# WS2812B-strip.net
KiCad netlist of a schematic drawn in EAGLE
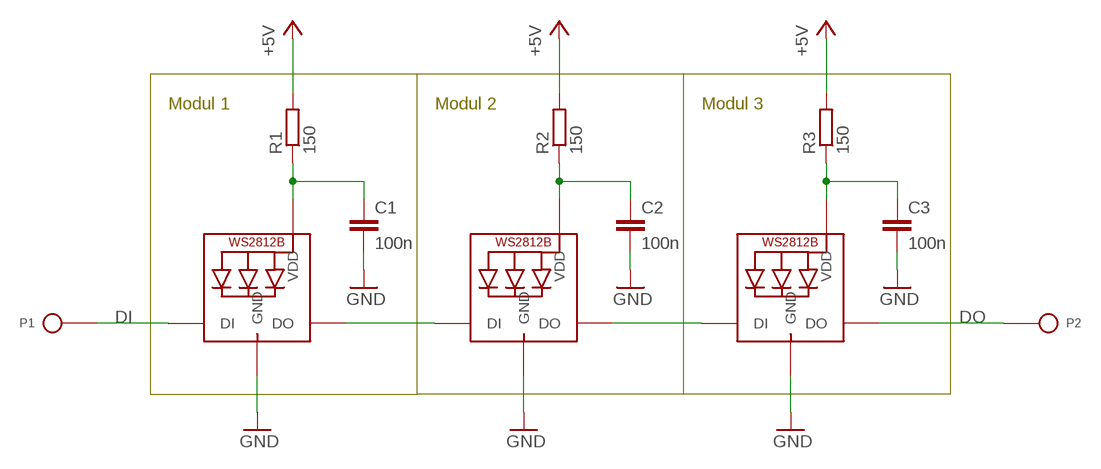
[diagram p0: schematic, sheet 1]

(export (version "E")
  (design (tool "Eeschema 10.0.6"))
  (components
    (comp (ref "C1")
      (value "100n")
      (footprint "eagle-import:C0805")
      (libsource (lib "eagle-import") (part "C-EUC0805"))
    )
    (comp (ref "C2")
      (value "100n")
      (footprint "eagle-import:C0805")
      (libsource (lib "eagle-import") (part "C-EUC0805"))
    )
    (comp (ref "C3")
      (value "100n")
      (footprint "eagle-import:C0805")
      (libsource (lib "eagle-import") (part "C-EUC0805"))
    )
    (comp (ref "LED1")
      (value "WS2812B3535")
      (footprint "eagle-import:LED3535")
      (libsource (lib "eagle-import") (part "WS2812B3535"))
    )
    (comp (ref "LED2")
      (value "WS2812B3535")
      (footprint "eagle-import:LED3535")
      (libsource (lib "eagle-import") (part "WS2812B3535"))
    )
    (comp (ref "LED3")
      (value "WS2812B3535")
      (footprint "eagle-import:LED3535")
      (libsource (lib "eagle-import") (part "WS2812B3535"))
    )
    (comp (ref "P1")
      (value "RUPAVELIKA")
      (footprint "eagle-import:RUPA2.54")
      (libsource (lib "eagle-import") (part "RUPAVELIKA"))
    )
    (comp (ref "P2")
      (value "RUPAVELIKA")
      (footprint "eagle-import:RUPA2.54")
      (libsource (lib "eagle-import") (part "RUPAVELIKA"))
    )
    (comp (ref "R1")
      (value "150")
      (footprint "eagle-import:R0805")
      (libsource (lib "eagle-import") (part "R-EU_R0805"))
    )
    (comp (ref "R2")
      (value "150")
      (footprint "eagle-import:R0805")
      (libsource (lib "eagle-import") (part "R-EU_R0805"))
    )
    (comp (ref "R3")
      (value "150")
      (footprint "eagle-import:R0805")
      (libsource (lib "eagle-import") (part "R-EU_R0805"))
    )
  )
  (nets
    (net (code "1") (name "+5V") (class "Default")
      (node (ref "R1") (pin "2") (pinfunction "2_2") (pintype "passive"))
      (node (ref "R2") (pin "2") (pinfunction "2_2") (pintype "passive"))
      (node (ref "R3") (pin "2") (pinfunction "2_2") (pintype "passive"))
    )
    (net (code "2") (name "/DI") (class "Default")
      (node (ref "LED1") (pin "1") (pinfunction "DI_1") (pintype "input"))
      (node (ref "P1") (pin "P$1") (pinfunction "P_P$1") (pintype "bidirectional"))
    )
    (net (code "3") (name "/DO") (class "Default")
      (node (ref "LED3") (pin "3") (pinfunction "DO_3") (pintype "output"))
      (node (ref "P2") (pin "P$1") (pinfunction "P_P$1") (pintype "bidirectional"))
    )
    (net (code "4") (name "GND") (class "Default")
      (node (ref "C1") (pin "2") (pinfunction "2_2") (pintype "passive"))
      (node (ref "C2") (pin "2") (pinfunction "2_2") (pintype "passive"))
      (node (ref "C3") (pin "2") (pinfunction "2_2") (pintype "passive"))
      (node (ref "LED1") (pin "4") (pinfunction "GND_4") (pintype "power_in"))
      (node (ref "LED2") (pin "4") (pinfunction "GND_4") (pintype "power_in"))
      (node (ref "LED3") (pin "4") (pinfunction "GND_4") (pintype "power_in"))
    )
    (net (code "5") (name "Net-(LED1-DO)") (class "Default")
      (node (ref "LED1") (pin "3") (pinfunction "DO_3") (pintype "output"))
      (node (ref "LED2") (pin "1") (pinfunction "DI_1") (pintype "input"))
    )
    (net (code "6") (name "Net-(LED1-VDD)") (class "Default")
      (node (ref "C1") (pin "1") (pinfunction "1_1") (pintype "passive"))
      (node (ref "LED1") (pin "2") (pinfunction "VDD_2") (pintype "power_in"))
      (node (ref "R1") (pin "1") (pinfunction "1_1") (pintype "passive"))
    )
    (net (code "7") (name "Net-(LED2-DO)") (class "Default")
      (node (ref "LED2") (pin "3") (pinfunction "DO_3") (pintype "output"))
      (node (ref "LED3") (pin "1") (pinfunction "DI_1") (pintype "input"))
    )
    (net (code "8") (name "Net-(LED2-VDD)") (class "Default")
      (node (ref "C2") (pin "1") (pinfunction "1_1") (pintype "passive"))
      (node (ref "LED2") (pin "2") (pinfunction "VDD_2") (pintype "power_in"))
      (node (ref "R2") (pin "1") (pinfunction "1_1") (pintype "passive"))
    )
    (net (code "9") (name "Net-(LED3-VDD)") (class "Default")
      (node (ref "C3") (pin "1") (pinfunction "1_1") (pintype "passive"))
      (node (ref "LED3") (pin "2") (pinfunction "VDD_2") (pintype "power_in"))
      (node (ref "R3") (pin "1") (pinfunction "1_1") (pintype "passive"))
    )
  )
)
